# quadcopter.net
KiCad netlist of a schematic drawn in EAGLE
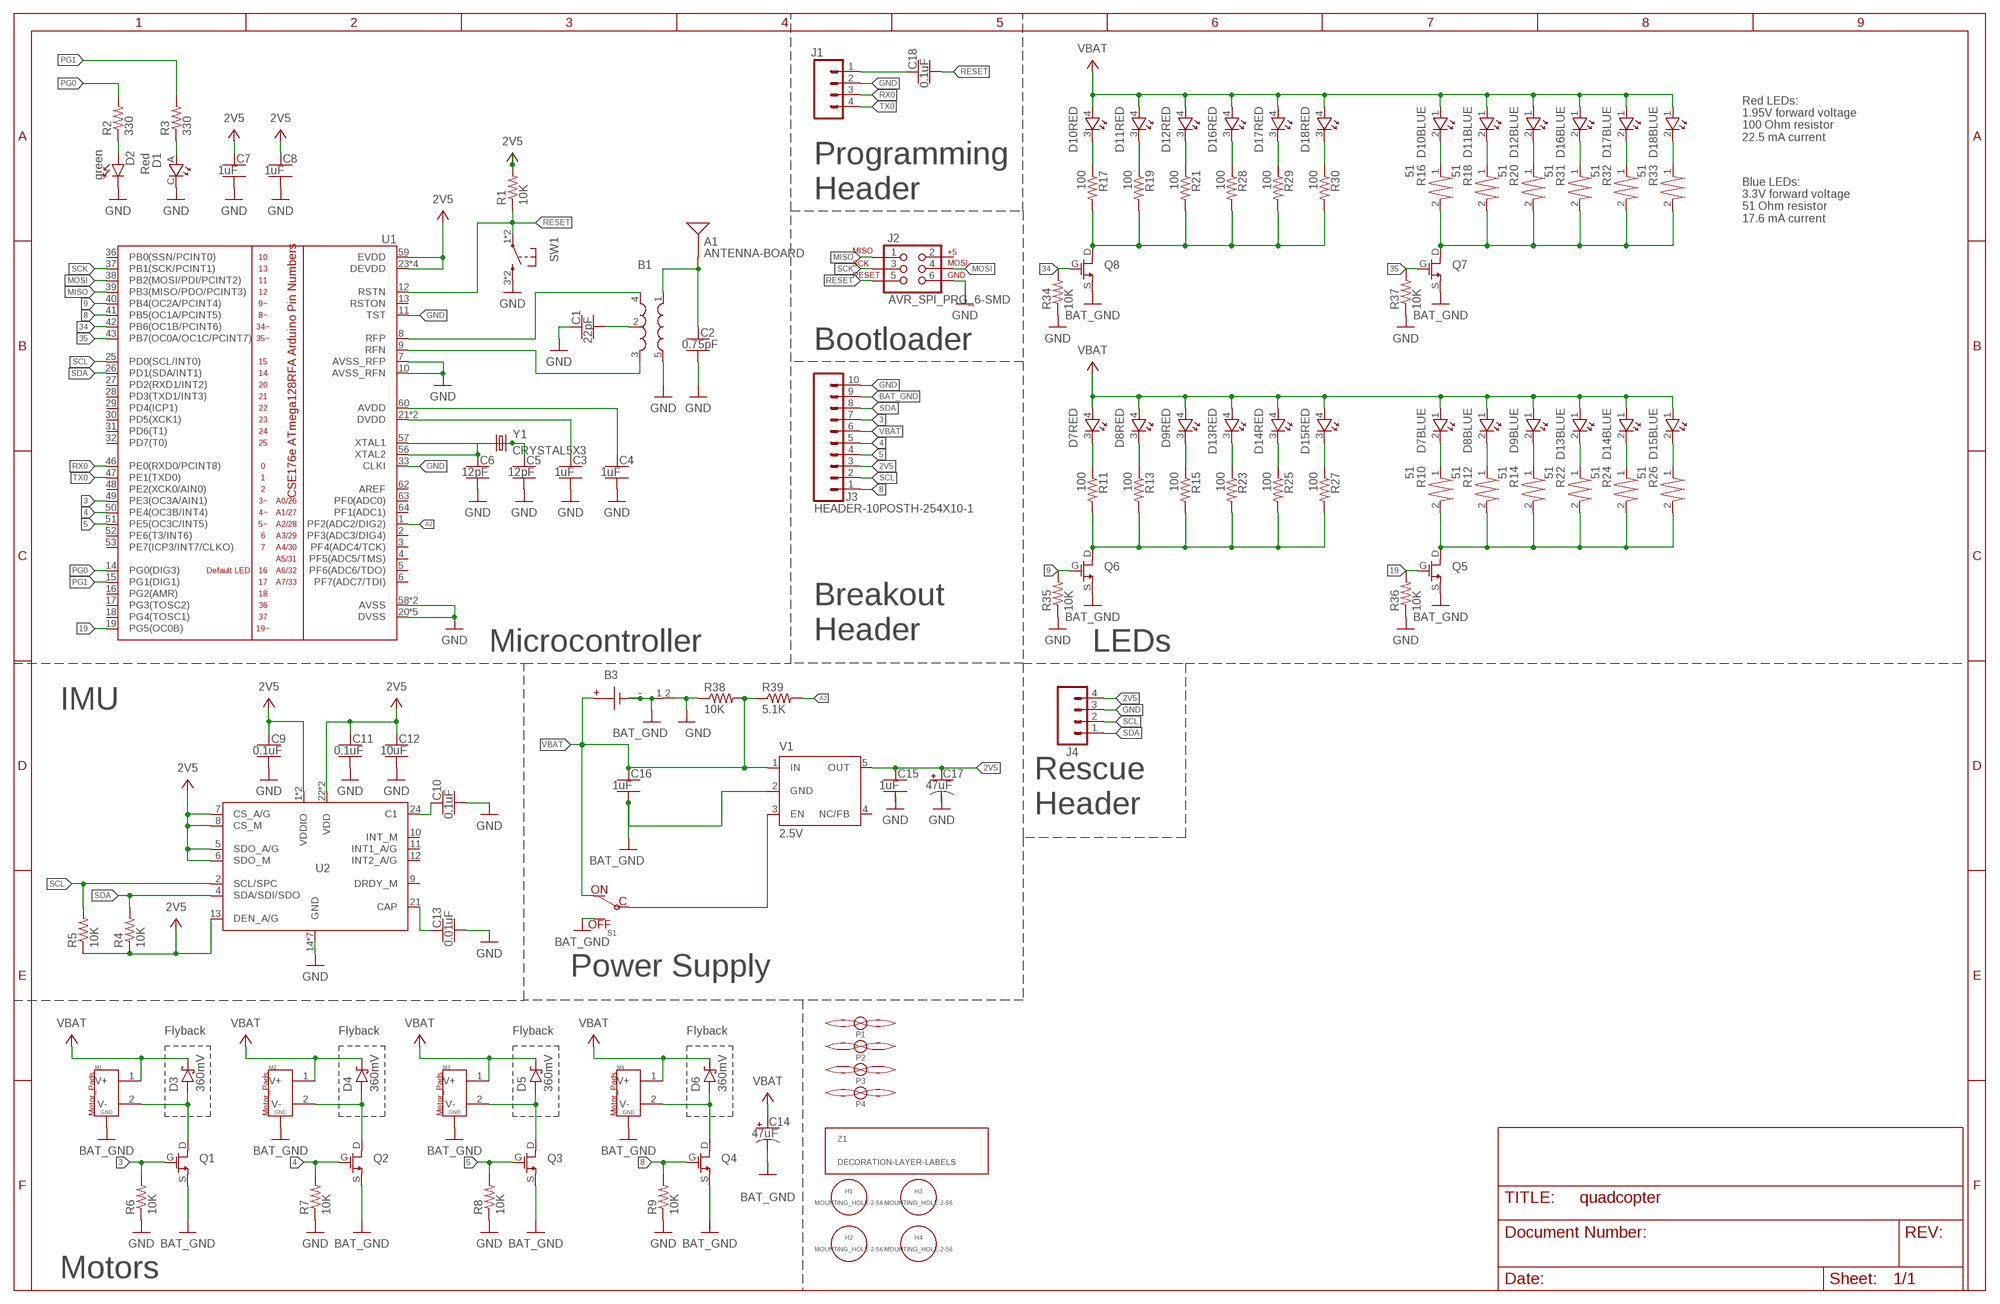
[diagram p0: schematic, sheet 1]

(export (version "E")
  (design (tool "Eeschema 10.0.6"))
  (components
    (comp (ref "A1")
      (value "ANTENNA-BOARD")
      (footprint "eagle-import:ANT_PCB_2.4GHZ_NRF8001_1.6MM_1OZ")
      (fields (field (name "MFR") "NA") (field (name "CREATOR") "Swanson"))
      (libsource (lib "eagle-import") (part "ANTENNA-BOARD"))
    )
    (comp (ref "B1")
      (value "BALUN0805")
      (footprint "eagle-import:BALUN")
      (fields
        (field (name "MFR") "Wurth Electronics Inc.")
        (field (name "MPN") "748421245")
        (field (name "CREATOR") "Swanson")
        (field (name "REVIEWER") "Swanson")
      )
      (libsource (lib "eagle-import") (part "BALUN0805"))
    )
    (comp (ref "B3")
      (value "BATTERY-SMD-TH")
      (footprint "eagle-import:BATTERY-COMBO")
      (libsource (lib "eagle-import") (part "BATTERY-SMD-TH"))
    )
    (comp (ref "C1")
      (value "22pF")
      (footprint "eagle-import:CAPC2012X140_HS")
      (fields
        (field (name "MFR") "Murata Electronics")
        (field (name "MPN") "GRM21A5C2E220JW01D")
        (field (name "CREATOR") "Swanson")
        (field (name "REVIEWER") "Swanson")
      )
      (libsource (lib "eagle-import") (part "CAPACITOR-NP_SMD-2012-0805_CERAMIC-22PF"))
    )
    (comp (ref "C2")
      (value "0.75pF")
      (footprint "eagle-import:CAPC2012X140_HS")
      (fields
        (field (name "MFR") "Murata Electronics")
        (field (name "MPN") "GQM2195C2AR75CB01D")
        (field (name "CREATOR") "Swanson")
        (field (name "REVIEWER") "Swanson")
      )
      (libsource (lib "eagle-import") (part "CAPACITOR-NP_SMD-2012-0805_CERAMIC-0.75PF"))
    )
    (comp (ref "C3")
      (value "1uF")
      (footprint "eagle-import:CAPC2012X140_HS")
      (fields
        (field (name "MFR") "Taiyo Yuden")
        (field (name "MPN") "TMK212B7105KG-T")
        (field (name "CREATOR") "Swanson")
        (field (name "REVIEWER") "Swanson")
      )
      (libsource (lib "eagle-import") (part "CAPACITOR-NP_SMD-2012-0805_CERAMIC-1UF"))
    )
    (comp (ref "C4")
      (value "1uF")
      (footprint "eagle-import:CAPC2012X140_HS")
      (fields
        (field (name "MFR") "Taiyo Yuden")
        (field (name "MPN") "TMK212B7105KG-T")
        (field (name "CREATOR") "Swanson")
        (field (name "REVIEWER") "Swanson")
      )
      (libsource (lib "eagle-import") (part "CAPACITOR-NP_SMD-2012-0805_CERAMIC-1UF"))
    )
    (comp (ref "C5")
      (value "12pF")
      (footprint "eagle-import:CAPC2012X140_HS")
      (fields
        (field (name "MFR") "Murata Electronics")
        (field (name "MPN") "GRM21A5C2E120JW01D")
        (field (name "CREATOR") "Swanson")
        (field (name "REVIEWER") "Swanson")
      )
      (libsource (lib "eagle-import") (part "CAPACITOR-NP_SMD-2012-0805_CERAMIC-12PF"))
    )
    (comp (ref "C6")
      (value "12pF")
      (footprint "eagle-import:CAPC2012X140_HS")
      (fields
        (field (name "MFR") "Murata Electronics")
        (field (name "MPN") "GRM21A5C2E120JW01D")
        (field (name "CREATOR") "Swanson")
        (field (name "REVIEWER") "Swanson")
      )
      (libsource (lib "eagle-import") (part "CAPACITOR-NP_SMD-2012-0805_CERAMIC-12PF"))
    )
    (comp (ref "C7")
      (value "1uF")
      (footprint "eagle-import:CAPC2012X140_HS")
      (fields
        (field (name "MFR") "Taiyo Yuden")
        (field (name "MPN") "TMK212B7105KG-T")
        (field (name "CREATOR") "Swanson")
        (field (name "REVIEWER") "Swanson")
      )
      (libsource (lib "eagle-import") (part "CAPACITOR-NP_SMD-2012-0805_CERAMIC-1UF"))
    )
    (comp (ref "C8")
      (value "1uF")
      (footprint "eagle-import:CAPC2012X140_HS")
      (fields
        (field (name "MFR") "Taiyo Yuden")
        (field (name "MPN") "TMK212B7105KG-T")
        (field (name "CREATOR") "Swanson")
        (field (name "REVIEWER") "Swanson")
      )
      (libsource (lib "eagle-import") (part "CAPACITOR-NP_SMD-2012-0805_CERAMIC-1UF"))
    )
    (comp (ref "C9")
      (value "0.1uF")
      (footprint "eagle-import:CAPC2012X140_HS")
      (fields
        (field (name "MFR") "TDK Corporation")
        (field (name "MPN") "C2012X7R2A104K125AA")
        (field (name "CREATOR") "Swanson")
        (field (name "REVIEWER") "Swanson")
      )
      (libsource (lib "eagle-import") (part "CAPACITOR-NP_SMD-2012-0805_CERAMIC-0.1UF"))
    )
    (comp (ref "C10")
      (value "0.1uF")
      (footprint "eagle-import:CAPC2012X140_HS")
      (fields
        (field (name "MFR") "TDK Corporation")
        (field (name "MPN") "C2012X7R2A104K125AA")
        (field (name "CREATOR") "Swanson")
        (field (name "REVIEWER") "Swanson")
      )
      (libsource (lib "eagle-import") (part "CAPACITOR-NP_SMD-2012-0805_CERAMIC-0.1UF"))
    )
    (comp (ref "C11")
      (value "0.1uF")
      (footprint "eagle-import:CAPC2012X140_HS")
      (fields
        (field (name "MFR") "TDK Corporation")
        (field (name "MPN") "C2012X7R2A104K125AA")
        (field (name "CREATOR") "Swanson")
        (field (name "REVIEWER") "Swanson")
      )
      (libsource (lib "eagle-import") (part "CAPACITOR-NP_SMD-2012-0805_CERAMIC-0.1UF"))
    )
    (comp (ref "C12")
      (value "10uF")
      (footprint "eagle-import:CAPC2012X140_HS")
      (fields
        (field (name "MFR") "TDK")
        (field (name "MPN") "C2012X5R1E106K125AB")
        (field (name "CREATOR") "Swanson")
        (field (name "REVIEWER") "Swanson")
      )
      (libsource (lib "eagle-import") (part "CAPACITOR-NP_SMD-2012-0805_CERAMIC-10UF"))
    )
    (comp (ref "C13")
      (value "0.01uF")
      (footprint "eagle-import:CAPC2012X140_HS")
      (fields
        (field (name "MFR") "Knowles Syfer")
        (field (name "MPN") "0805J0500104KJT")
        (field (name "CREATOR") "Swanson")
        (field (name "REVIEWER") "Swanson")
      )
      (libsource (lib "eagle-import") (part "CAPACITOR-NP_SMD-2012-0805_CERAMIC-0.01UF"))
    )
    (comp (ref "C14")
      (value "47uF")
      (footprint "eagle-import:CAPMP3216X180")
      (fields
        (field (name "MFR") "AVX Corporation")
        (field (name "MPN") "TAJA476K006SNJV")
        (field (name "CREATOR") "Swanson")
      )
      (libsource (lib "eagle-import") (part "CAPACITOR-POL_47UF-SMD-1206-TAJA"))
    )
    (comp (ref "C15")
      (value "1uF")
      (footprint "eagle-import:CAPC2012X140_HS")
      (fields
        (field (name "MFR") "Taiyo Yuden")
        (field (name "MPN") "TMK212B7105KG-T")
        (field (name "CREATOR") "Swanson")
        (field (name "REVIEWER") "Swanson")
      )
      (libsource (lib "eagle-import") (part "CAPACITOR-NP_SMD-2012-0805_CERAMIC-1UF"))
    )
    (comp (ref "C16")
      (value "1uF")
      (footprint "eagle-import:CAPC2012X140_HS")
      (fields
        (field (name "MFR") "Taiyo Yuden")
        (field (name "MPN") "TMK212B7105KG-T")
        (field (name "CREATOR") "Swanson")
        (field (name "REVIEWER") "Swanson")
      )
      (libsource (lib "eagle-import") (part "CAPACITOR-NP_SMD-2012-0805_CERAMIC-1UF"))
    )
    (comp (ref "C17")
      (value "47uF")
      (footprint "eagle-import:CAPMP3216X180")
      (fields
        (field (name "MFR") "AVX Corporation")
        (field (name "MPN") "TAJA476K006SNJV")
        (field (name "CREATOR") "Swanson")
      )
      (libsource (lib "eagle-import") (part "CAPACITOR-POL_47UF-SMD-1206-TAJA"))
    )
    (comp (ref "C18")
      (value "0.1uF")
      (footprint "eagle-import:CAPC2012X140_HS")
      (fields
        (field (name "MFR") "TDK Corporation")
        (field (name "MPN") "C2012X7R2A104K125AA")
        (field (name "CREATOR") "Swanson")
        (field (name "REVIEWER") "Swanson")
      )
      (libsource (lib "eagle-import") (part "CAPACITOR-NP_SMD-2012-0805_CERAMIC-0.1UF"))
    )
    (comp (ref "D1")
      (value "Red")
      (footprint "eagle-import:0805_LED")
      (fields (field (name "CREATOR") "Rye Gleason"))
      (libsource (lib "eagle-import") (part "LED-RED-0805"))
    )
    (comp (ref "D2")
      (value "green")
      (footprint "eagle-import:LEDSC125X200X120-2_HS")
      (fields
        (field (name "MFR") "Lite-On Inc")
        (field (name "MPN") "LTST-C170GKT")
        (field (name "CREATOR") "Swanson")
        (field (name "REVIEWER") "Swanson")
      )
      (libsource (lib "eagle-import") (part "DIODE-LED_SMD-2012-0805-GREEN"))
    )
    (comp (ref "D3")
      (value "360mV")
      (footprint "eagle-import:SODFL3516X96")
      (fields
        (field (name "MFR") "Toshiba Semiconductor and Storage")
        (field (name "MPN") "CRS08(TE85L,Q,M)")
        (field (name "CREATOR") "Swanson")
        (field (name "REVIEWER") "Swanson")
      )
      (libsource (lib "eagle-import") (part "DIODE-SCHOTTKY_-SMD-SOD123"))
    )
    (comp (ref "D4")
      (value "360mV")
      (footprint "eagle-import:SODFL3516X96")
      (fields
        (field (name "MFR") "Toshiba Semiconductor and Storage")
        (field (name "MPN") "CRS08(TE85L,Q,M)")
        (field (name "CREATOR") "Swanson")
        (field (name "REVIEWER") "Swanson")
      )
      (libsource (lib "eagle-import") (part "DIODE-SCHOTTKY_-SMD-SOD123"))
    )
    (comp (ref "D5")
      (value "360mV")
      (footprint "eagle-import:SODFL3516X96")
      (fields
        (field (name "MFR") "Toshiba Semiconductor and Storage")
        (field (name "MPN") "CRS08(TE85L,Q,M)")
        (field (name "CREATOR") "Swanson")
        (field (name "REVIEWER") "Swanson")
      )
      (libsource (lib "eagle-import") (part "DIODE-SCHOTTKY_-SMD-SOD123"))
    )
    (comp (ref "D6")
      (value "360mV")
      (footprint "eagle-import:SODFL3516X96")
      (fields
        (field (name "MFR") "Toshiba Semiconductor and Storage")
        (field (name "MPN") "CRS08(TE85L,Q,M)")
        (field (name "CREATOR") "Swanson")
        (field (name "REVIEWER") "Swanson")
      )
      (libsource (lib "eagle-import") (part "DIODE-SCHOTTKY_-SMD-SOD123"))
    )
    (comp (ref "D7")
      (value "DUAL_LED0805_RB_LED")
      (footprint "eagle-import:0805_RB_LED")
      (fields (field (name "CREATOR") "Rye Gleason"))
      (libsource (lib "eagle-import") (part "DUAL_LED0805_RB_LED"))
    )
    (comp (ref "D8")
      (value "DUAL_LED0805_RB_LED")
      (footprint "eagle-import:0805_RB_LED")
      (fields (field (name "CREATOR") "Rye Gleason"))
      (libsource (lib "eagle-import") (part "DUAL_LED0805_RB_LED"))
    )
    (comp (ref "D9")
      (value "DUAL_LED0805_RB_LED")
      (footprint "eagle-import:0805_RB_LED")
      (fields (field (name "CREATOR") "Rye Gleason"))
      (libsource (lib "eagle-import") (part "DUAL_LED0805_RB_LED"))
    )
    (comp (ref "D10")
      (value "DUAL_LED0805_RB_LED")
      (footprint "eagle-import:0805_RB_LED")
      (fields (field (name "CREATOR") "Rye Gleason"))
      (libsource (lib "eagle-import") (part "DUAL_LED0805_RB_LED"))
    )
    (comp (ref "D11")
      (value "DUAL_LED0805_RB_LED")
      (footprint "eagle-import:0805_RB_LED")
      (fields (field (name "CREATOR") "Rye Gleason"))
      (libsource (lib "eagle-import") (part "DUAL_LED0805_RB_LED"))
    )
    (comp (ref "D12")
      (value "DUAL_LED0805_RB_LED")
      (footprint "eagle-import:0805_RB_LED")
      (fields (field (name "CREATOR") "Rye Gleason"))
      (libsource (lib "eagle-import") (part "DUAL_LED0805_RB_LED"))
    )
    (comp (ref "D13")
      (value "DUAL_LED0805_RB_LED")
      (footprint "eagle-import:0805_RB_LED")
      (fields (field (name "CREATOR") "Rye Gleason"))
      (libsource (lib "eagle-import") (part "DUAL_LED0805_RB_LED"))
    )
    (comp (ref "D14")
      (value "DUAL_LED0805_RB_LED")
      (footprint "eagle-import:0805_RB_LED")
      (fields (field (name "CREATOR") "Rye Gleason"))
      (libsource (lib "eagle-import") (part "DUAL_LED0805_RB_LED"))
    )
    (comp (ref "D15")
      (value "DUAL_LED0805_RB_LED")
      (footprint "eagle-import:0805_RB_LED")
      (fields (field (name "CREATOR") "Rye Gleason"))
      (libsource (lib "eagle-import") (part "DUAL_LED0805_RB_LED"))
    )
    (comp (ref "D16")
      (value "DUAL_LED0805_RB_LED")
      (footprint "eagle-import:0805_RB_LED")
      (fields (field (name "CREATOR") "Rye Gleason"))
      (libsource (lib "eagle-import") (part "DUAL_LED0805_RB_LED"))
    )
    (comp (ref "D17")
      (value "DUAL_LED0805_RB_LED")
      (footprint "eagle-import:0805_RB_LED")
      (fields (field (name "CREATOR") "Rye Gleason"))
      (libsource (lib "eagle-import") (part "DUAL_LED0805_RB_LED"))
    )
    (comp (ref "D18")
      (value "DUAL_LED0805_RB_LED")
      (footprint "eagle-import:0805_RB_LED")
      (fields (field (name "CREATOR") "Rye Gleason"))
      (libsource (lib "eagle-import") (part "DUAL_LED0805_RB_LED"))
    )
    (comp (ref "H1")
      (value "MOUNTING_HOLE-2-56")
      (footprint "eagle-import:2-56-MOUNTING-HOLE-NO-METAL")
      (libsource (lib "eagle-import") (part "MOUNTING_HOLE-2-56"))
    )
    (comp (ref "H2")
      (value "MOUNTING_HOLE-2-56")
      (footprint "eagle-import:2-56-MOUNTING-HOLE-NO-METAL")
      (libsource (lib "eagle-import") (part "MOUNTING_HOLE-2-56"))
    )
    (comp (ref "H3")
      (value "MOUNTING_HOLE-2-56")
      (footprint "eagle-import:2-56-MOUNTING-HOLE-NO-METAL")
      (libsource (lib "eagle-import") (part "MOUNTING_HOLE-2-56"))
    )
    (comp (ref "H4")
      (value "MOUNTING_HOLE-2-56")
      (footprint "eagle-import:2-56-MOUNTING-HOLE-NO-METAL")
      (libsource (lib "eagle-import") (part "MOUNTING_HOLE-2-56"))
    )
    (comp (ref "J1")
      (value "HEADER-4POS-0.1IN-FEMALE-SMD-BOTTOM-ENTRY")
      (footprint "eagle-import:HEADER-1X4-BOTTOM-ENTRY")
      (fields
        (field (name "MFR") "TE Connectivity AMP Connectors")
        (field (name "MPN") "1241152-4")
        (field (name "CREATOR") "Swanson")
      )
      (libsource (lib "eagle-import") (part "HEADER-4POS-0.1IN-FEMALE-SMD-BOTTOM-ENTRY"))
    )
    (comp (ref "J2")
      (value "AVR_SPI_PRG_6-SMD")
      (footprint "eagle-import:2X3-SMD")
      (fields
        (field (name "MFR") "Amphenol ICC (FCI)")
        (field (name "MPN") "95278-101A06LF")
        (field (name "CREATOR") "Swanson")
      )
      (libsource (lib "eagle-import") (part "AVR_SPI_PRG_6-SMD"))
    )
    (comp (ref "J3")
      (value "HEADER-10POSTH-254X10-1")
      (footprint "eagle-import:HDRV10W63P254_10X1_2540X254H838_HS")
      (fields
        (field (name "MFR") "Amphenol FCI")
        (field (name "MPN") "68000-110HLF")
        (field (name "CREATOR") "Swanson")
        (field (name "REVIEWER") "Swanson")
      )
      (libsource (lib "eagle-import") (part "HEADER-10POSTH-254X10-1"))
    )
    (comp (ref "J4")
      (value "HEADER-4POS-0.1IN-FEMALE")
      (footprint "eagle-import:HDRVR4W80P254_1X4_1066X254X850B")
      (fields (field (name "CREATOR") "Swanson"))
      (libsource (lib "eagle-import") (part "HEADER-4POS-0.1IN-FEMALE"))
    )
    (comp (ref "M1")
      (value "MOTOR_PADS_GND-MOLEX-SMD")
      (footprint "eagle-import:MOLEX-0532610271")
      (fields
        (field (name "MFR") "Molex")
        (field (name "MPN") "532610271")
        (field (name "CREATOR") "Swanson")
      )
      (libsource (lib "eagle-import") (part "MOTOR_PADS_GND-MOLEX-SMD"))
    )
    (comp (ref "M2")
      (value "MOTOR_PADS_GND-MOLEX-SMD")
      (footprint "eagle-import:MOLEX-0532610271")
      (fields
        (field (name "MFR") "Molex")
        (field (name "MPN") "532610271")
        (field (name "CREATOR") "Swanson")
      )
      (libsource (lib "eagle-import") (part "MOTOR_PADS_GND-MOLEX-SMD"))
    )
    (comp (ref "M3")
      (value "MOTOR_PADS_GND-MOLEX-SMD")
      (footprint "eagle-import:MOLEX-0532610271")
      (fields
        (field (name "MFR") "Molex")
        (field (name "MPN") "532610271")
        (field (name "CREATOR") "Swanson")
      )
      (libsource (lib "eagle-import") (part "MOTOR_PADS_GND-MOLEX-SMD"))
    )
    (comp (ref "M4")
      (value "MOTOR_PADS_GND-MOLEX-SMD")
      (footprint "eagle-import:MOLEX-0532610271")
      (fields
        (field (name "MFR") "Molex")
        (field (name "MPN") "532610271")
        (field (name "CREATOR") "Swanson")
      )
      (libsource (lib "eagle-import") (part "MOTOR_PADS_GND-MOLEX-SMD"))
    )
    (comp (ref "P1")
      (value "PROPELLOR-45MM")
      (footprint "eagle-import:MOTOR_AND_PROP")
      (libsource (lib "eagle-import") (part "PROPELLOR-45MM"))
    )
    (comp (ref "P2")
      (value "PROPELLOR-45MM")
      (footprint "eagle-import:MOTOR_AND_PROP")
      (libsource (lib "eagle-import") (part "PROPELLOR-45MM"))
    )
    (comp (ref "P3")
      (value "PROPELLOR-45MM")
      (footprint "eagle-import:MOTOR_AND_PROP")
      (libsource (lib "eagle-import") (part "PROPELLOR-45MM"))
    )
    (comp (ref "P4")
      (value "PROPELLOR-45MM")
      (footprint "eagle-import:MOTOR_AND_PROP")
      (libsource (lib "eagle-import") (part "PROPELLOR-45MM"))
    )
    (comp (ref "Q1")
      (value "NMOSFETSI2302CDS-T1-E3CT-ND")
      (footprint "eagle-import:SOT23_MOSFET")
      (fields (field (name "CREATOR") "Rye Gleason"))
      (libsource (lib "eagle-import") (part "NMOSFETSI2302CDS-T1-E3CT-ND"))
    )
    (comp (ref "Q2")
      (value "NMOSFETSI2302CDS-T1-E3CT-ND")
      (footprint "eagle-import:SOT23_MOSFET")
      (fields (field (name "CREATOR") "Rye Gleason"))
      (libsource (lib "eagle-import") (part "NMOSFETSI2302CDS-T1-E3CT-ND"))
    )
    (comp (ref "Q3")
      (value "NMOSFETSI2302CDS-T1-E3CT-ND")
      (footprint "eagle-import:SOT23_MOSFET")
      (fields (field (name "CREATOR") "Rye Gleason"))
      (libsource (lib "eagle-import") (part "NMOSFETSI2302CDS-T1-E3CT-ND"))
    )
    (comp (ref "Q4")
      (value "NMOSFETSI2302CDS-T1-E3CT-ND")
      (footprint "eagle-import:SOT23_MOSFET")
      (fields (field (name "CREATOR") "Rye Gleason"))
      (libsource (lib "eagle-import") (part "NMOSFETSI2302CDS-T1-E3CT-ND"))
    )
    (comp (ref "Q5")
      (value "NMOSFETSI2302CDS-T1-E3CT-ND")
      (footprint "eagle-import:SOT23_MOSFET")
      (fields (field (name "CREATOR") "Rye Gleason"))
      (libsource (lib "eagle-import") (part "NMOSFETSI2302CDS-T1-E3CT-ND"))
    )
    (comp (ref "Q6")
      (value "NMOSFETSI2302CDS-T1-E3CT-ND")
      (footprint "eagle-import:SOT23_MOSFET")
      (fields (field (name "CREATOR") "Rye Gleason"))
      (libsource (lib "eagle-import") (part "NMOSFETSI2302CDS-T1-E3CT-ND"))
    )
    (comp (ref "Q7")
      (value "NMOSFETSI2302CDS-T1-E3CT-ND")
      (footprint "eagle-import:SOT23_MOSFET")
      (fields (field (name "CREATOR") "Rye Gleason"))
      (libsource (lib "eagle-import") (part "NMOSFETSI2302CDS-T1-E3CT-ND"))
    )
    (comp (ref "Q8")
      (value "NMOSFETSI2302CDS-T1-E3CT-ND")
      (footprint "eagle-import:SOT23_MOSFET")
      (fields (field (name "CREATOR") "Rye Gleason"))
      (libsource (lib "eagle-import") (part "NMOSFETSI2302CDS-T1-E3CT-ND"))
    )
    (comp (ref "R1")
      (value "10K")
      (footprint "eagle-import:RESC2012X60_HS")
      (fields
        (field (name "MFR") "Yageo")
        (field (name "MPN") "RC0805JR-0710KL")
        (field (name "CREATOR") "Swanson")
        (field (name "REVIEWER") "Swanson")
      )
      (libsource (lib "eagle-import") (part "RESISTOR_SMD-2012-0805-10K"))
    )
    (comp (ref "R2")
      (value "330")
      (footprint "eagle-import:RESC2012X60_HS")
      (fields
        (field (name "MFR") "Yageo")
        (field (name "MPN") "RC0805JR-07330RL")
        (field (name "CREATOR") "Swanson")
        (field (name "REVIEWER") "Swanson")
      )
      (libsource (lib "eagle-import") (part "RESISTOR_SMD-2012-0805-330"))
    )
    (comp (ref "R3")
      (value "330")
      (footprint "eagle-import:RESC2012X60_HS")
      (fields
        (field (name "MFR") "Yageo")
        (field (name "MPN") "RC0805JR-07330RL")
        (field (name "CREATOR") "Swanson")
        (field (name "REVIEWER") "Swanson")
      )
      (libsource (lib "eagle-import") (part "RESISTOR_SMD-2012-0805-330"))
    )
    (comp (ref "R4")
      (value "10K")
      (footprint "eagle-import:RESC2012X60_HS")
      (fields
        (field (name "MFR") "Yageo")
        (field (name "MPN") "RC0805JR-0710KL")
        (field (name "CREATOR") "Swanson")
        (field (name "REVIEWER") "Swanson")
      )
      (libsource (lib "eagle-import") (part "RESISTOR_SMD-2012-0805-10K"))
    )
    (comp (ref "R5")
      (value "10K")
      (footprint "eagle-import:RESC2012X60_HS")
      (fields
        (field (name "MFR") "Yageo")
        (field (name "MPN") "RC0805JR-0710KL")
        (field (name "CREATOR") "Swanson")
        (field (name "REVIEWER") "Swanson")
      )
      (libsource (lib "eagle-import") (part "RESISTOR_SMD-2012-0805-10K"))
    )
    (comp (ref "R6")
      (value "10K")
      (footprint "eagle-import:RESC2012X60_HS")
      (fields
        (field (name "MFR") "Yageo")
        (field (name "MPN") "RC0805JR-0710KL")
        (field (name "CREATOR") "Swanson")
        (field (name "REVIEWER") "Swanson")
      )
      (libsource (lib "eagle-import") (part "RESISTOR_SMD-2012-0805-10K"))
    )
    (comp (ref "R7")
      (value "10K")
      (footprint "eagle-import:RESC2012X60_HS")
      (fields
        (field (name "MFR") "Yageo")
        (field (name "MPN") "RC0805JR-0710KL")
        (field (name "CREATOR") "Swanson")
        (field (name "REVIEWER") "Swanson")
      )
      (libsource (lib "eagle-import") (part "RESISTOR_SMD-2012-0805-10K"))
    )
    (comp (ref "R8")
      (value "10K")
      (footprint "eagle-import:RESC2012X60_HS")
      (fields
        (field (name "MFR") "Yageo")
        (field (name "MPN") "RC0805JR-0710KL")
        (field (name "CREATOR") "Swanson")
        (field (name "REVIEWER") "Swanson")
      )
      (libsource (lib "eagle-import") (part "RESISTOR_SMD-2012-0805-10K"))
    )
    (comp (ref "R9")
      (value "10K")
      (footprint "eagle-import:RESC2012X60_HS")
      (fields
        (field (name "MFR") "Yageo")
        (field (name "MPN") "RC0805JR-0710KL")
        (field (name "CREATOR") "Swanson")
        (field (name "REVIEWER") "Swanson")
      )
      (libsource (lib "eagle-import") (part "RESISTOR_SMD-2012-0805-10K"))
    )
    (comp (ref "R10")
      (value "51")
      (footprint "eagle-import:0805_RESISTOR")
      (fields (field (name "CREATOR") "Rye Gleason"))
      (libsource (lib "eagle-import") (part "RESISTOR-0805-51OHM"))
    )
    (comp (ref "R11")
      (value "100")
      (footprint "eagle-import:RESC2012X60_HS")
      (fields
        (field (name "MFR") "Yageo")
        (field (name "MPN") "RC0805JR-07100RL")
        (field (name "CREATOR") "Swanson")
        (field (name "REVIEWER") "Swanson")
      )
      (libsource (lib "eagle-import") (part "RESISTOR_SMD-2012-0805-100"))
    )
    (comp (ref "R12")
      (value "51")
      (footprint "eagle-import:0805_RESISTOR")
      (fields (field (name "CREATOR") "Rye Gleason"))
      (libsource (lib "eagle-import") (part "RESISTOR-0805-51OHM"))
    )
    (comp (ref "R13")
      (value "100")
      (footprint "eagle-import:RESC2012X60_HS")
      (fields
        (field (name "MFR") "Yageo")
        (field (name "MPN") "RC0805JR-07100RL")
        (field (name "CREATOR") "Swanson")
        (field (name "REVIEWER") "Swanson")
      )
      (libsource (lib "eagle-import") (part "RESISTOR_SMD-2012-0805-100"))
    )
    (comp (ref "R14")
      (value "51")
      (footprint "eagle-import:0805_RESISTOR")
      (fields (field (name "CREATOR") "Rye Gleason"))
      (libsource (lib "eagle-import") (part "RESISTOR-0805-51OHM"))
    )
    (comp (ref "R15")
      (value "100")
      (footprint "eagle-import:RESC2012X60_HS")
      (fields
        (field (name "MFR") "Yageo")
        (field (name "MPN") "RC0805JR-07100RL")
        (field (name "CREATOR") "Swanson")
        (field (name "REVIEWER") "Swanson")
      )
      (libsource (lib "eagle-import") (part "RESISTOR_SMD-2012-0805-100"))
    )
    (comp (ref "R16")
      (value "51")
      (footprint "eagle-import:0805_RESISTOR")
      (fields (field (name "CREATOR") "Rye Gleason"))
      (libsource (lib "eagle-import") (part "RESISTOR-0805-51OHM"))
    )
    (comp (ref "R17")
      (value "100")
      (footprint "eagle-import:RESC2012X60_HS")
      (fields
        (field (name "MFR") "Yageo")
        (field (name "MPN") "RC0805JR-07100RL")
        (field (name "CREATOR") "Swanson")
        (field (name "REVIEWER") "Swanson")
      )
      (libsource (lib "eagle-import") (part "RESISTOR_SMD-2012-0805-100"))
    )
    (comp (ref "R18")
      (value "51")
      (footprint "eagle-import:0805_RESISTOR")
      (fields (field (name "CREATOR") "Rye Gleason"))
      (libsource (lib "eagle-import") (part "RESISTOR-0805-51OHM"))
    )
    (comp (ref "R19")
      (value "100")
      (footprint "eagle-import:RESC2012X60_HS")
      (fields
        (field (name "MFR") "Yageo")
        (field (name "MPN") "RC0805JR-07100RL")
        (field (name "CREATOR") "Swanson")
        (field (name "REVIEWER") "Swanson")
      )
      (libsource (lib "eagle-import") (part "RESISTOR_SMD-2012-0805-100"))
    )
    (comp (ref "R20")
      (value "51")
      (footprint "eagle-import:0805_RESISTOR")
      (fields (field (name "CREATOR") "Rye Gleason"))
      (libsource (lib "eagle-import") (part "RESISTOR-0805-51OHM"))
    )
    (comp (ref "R21")
      (value "100")
      (footprint "eagle-import:RESC2012X60_HS")
      (fields
        (field (name "MFR") "Yageo")
        (field (name "MPN") "RC0805JR-07100RL")
        (field (name "CREATOR") "Swanson")
        (field (name "REVIEWER") "Swanson")
      )
      (libsource (lib "eagle-import") (part "RESISTOR_SMD-2012-0805-100"))
    )
    (comp (ref "R22")
      (value "51")
      (footprint "eagle-import:0805_RESISTOR")
      (fields (field (name "CREATOR") "Rye Gleason"))
      (libsource (lib "eagle-import") (part "RESISTOR-0805-51OHM"))
    )
    (comp (ref "R23")
      (value "100")
      (footprint "eagle-import:RESC2012X60_HS")
      (fields
        (field (name "MFR") "Yageo")
        (field (name "MPN") "RC0805JR-07100RL")
        (field (name "CREATOR") "Swanson")
        (field (name "REVIEWER") "Swanson")
      )
      (libsource (lib "eagle-import") (part "RESISTOR_SMD-2012-0805-100"))
    )
    (comp (ref "R24")
      (value "51")
      (footprint "eagle-import:0805_RESISTOR")
      (fields (field (name "CREATOR") "Rye Gleason"))
      (libsource (lib "eagle-import") (part "RESISTOR-0805-51OHM"))
    )
    (comp (ref "R25")
      (value "100")
      (footprint "eagle-import:RESC2012X60_HS")
      (fields
        (field (name "MFR") "Yageo")
        (field (name "MPN") "RC0805JR-07100RL")
        (field (name "CREATOR") "Swanson")
        (field (name "REVIEWER") "Swanson")
      )
      (libsource (lib "eagle-import") (part "RESISTOR_SMD-2012-0805-100"))
    )
    (comp (ref "R26")
      (value "51")
      (footprint "eagle-import:0805_RESISTOR")
      (fields (field (name "CREATOR") "Rye Gleason"))
      (libsource (lib "eagle-import") (part "RESISTOR-0805-51OHM"))
    )
    (comp (ref "R27")
      (value "100")
      (footprint "eagle-import:RESC2012X60_HS")
      (fields
        (field (name "MFR") "Yageo")
        (field (name "MPN") "RC0805JR-07100RL")
        (field (name "CREATOR") "Swanson")
        (field (name "REVIEWER") "Swanson")
      )
      (libsource (lib "eagle-import") (part "RESISTOR_SMD-2012-0805-100"))
    )
    (comp (ref "R28")
      (value "100")
      (footprint "eagle-import:RESC2012X60_HS")
      (fields
        (field (name "MFR") "Yageo")
        (field (name "MPN") "RC0805JR-07100RL")
        (field (name "CREATOR") "Swanson")
        (field (name "REVIEWER") "Swanson")
      )
      (libsource (lib "eagle-import") (part "RESISTOR_SMD-2012-0805-100"))
    )
    (comp (ref "R29")
      (value "100")
      (footprint "eagle-import:RESC2012X60_HS")
      (fields
        (field (name "MFR") "Yageo")
        (field (name "MPN") "RC0805JR-07100RL")
        (field (name "CREATOR") "Swanson")
        (field (name "REVIEWER") "Swanson")
      )
      (libsource (lib "eagle-import") (part "RESISTOR_SMD-2012-0805-100"))
    )
    (comp (ref "R30")
      (value "100")
      (footprint "eagle-import:RESC2012X60_HS")
      (fields
        (field (name "MFR") "Yageo")
        (field (name "MPN") "RC0805JR-07100RL")
        (field (name "CREATOR") "Swanson")
        (field (name "REVIEWER") "Swanson")
      )
      (libsource (lib "eagle-import") (part "RESISTOR_SMD-2012-0805-100"))
    )
    (comp (ref "R31")
      (value "51")
      (footprint "eagle-import:0805_RESISTOR")
      (fields (field (name "CREATOR") "Rye Gleason"))
      (libsource (lib "eagle-import") (part "RESISTOR-0805-51OHM"))
    )
    (comp (ref "R32")
      (value "51")
      (footprint "eagle-import:0805_RESISTOR")
      (fields (field (name "CREATOR") "Rye Gleason"))
      (libsource (lib "eagle-import") (part "RESISTOR-0805-51OHM"))
    )
    (comp (ref "R33")
      (value "51")
      (footprint "eagle-import:0805_RESISTOR")
      (fields (field (name "CREATOR") "Rye Gleason"))
      (libsource (lib "eagle-import") (part "RESISTOR-0805-51OHM"))
    )
    (comp (ref "R34")
      (value "10K")
      (footprint "eagle-import:RESC2012X60_HS")
      (fields
        (field (name "MFR") "Yageo")
        (field (name "MPN") "RC0805JR-0710KL")
        (field (name "CREATOR") "Swanson")
        (field (name "REVIEWER") "Swanson")
      )
      (libsource (lib "eagle-import") (part "RESISTOR_SMD-2012-0805-10K"))
    )
    (comp (ref "R35")
      (value "10K")
      (footprint "eagle-import:RESC2012X60_HS")
      (fields
        (field (name "MFR") "Yageo")
        (field (name "MPN") "RC0805JR-0710KL")
        (field (name "CREATOR") "Swanson")
        (field (name "REVIEWER") "Swanson")
      )
      (libsource (lib "eagle-import") (part "RESISTOR_SMD-2012-0805-10K"))
    )
    (comp (ref "R36")
      (value "10K")
      (footprint "eagle-import:RESC2012X60_HS")
      (fields
        (field (name "MFR") "Yageo")
        (field (name "MPN") "RC0805JR-0710KL")
        (field (name "CREATOR") "Swanson")
        (field (name "REVIEWER") "Swanson")
      )
      (libsource (lib "eagle-import") (part "RESISTOR_SMD-2012-0805-10K"))
    )
    (comp (ref "R37")
      (value "10K")
      (footprint "eagle-import:RESC2012X60_HS")
      (fields
        (field (name "MFR") "Yageo")
        (field (name "MPN") "RC0805JR-0710KL")
        (field (name "CREATOR") "Swanson")
        (field (name "REVIEWER") "Swanson")
      )
      (libsource (lib "eagle-import") (part "RESISTOR_SMD-2012-0805-10K"))
    )
    (comp (ref "R38")
      (value "10K")
      (footprint "eagle-import:RESC2012X60_HS")
      (fields
        (field (name "MFR") "Yageo")
        (field (name "MPN") "RC0805JR-0710KL")
        (field (name "CREATOR") "Swanson")
        (field (name "REVIEWER") "Swanson")
      )
      (libsource (lib "eagle-import") (part "RESISTOR_SMD-2012-0805-10K"))
    )
    (comp (ref "R39")
      (value "5.1K")
      (footprint "eagle-import:RESC2012X60_HS")
      (fields
        (field (name "MFR") "Yageo")
        (field (name "MPN") "RC0805JR-075K1L")
        (field (name "CREATOR") "Swanson")
        (field (name "REVIEWER") "Swanson")
      )
      (libsource (lib "eagle-import") (part "RESISTOR_SMD-2012-0805-5.1K"))
    )
    (comp (ref "S1")
      (value "POWER-SWITCH-MFS201N-9-Z-SMD-EDGE")
      (footprint "eagle-import:JS102011SAQN")
      (fields
        (field (name "MFR") "C&K")
        (field (name "MPN") "JS102011SAQN")
        (field (name "CREATOR") "Swanson")
      )
      (libsource (lib "eagle-import") (part "POWER-SWITCH-MFS201N-9-Z-SMD-EDGE"))
    )
    (comp (ref "SW1")
      (value "PUSHBUTTON_-4.5X4.5")
      (footprint "eagle-import:4.5MM_TACTILE_SWITCH_TL3305AF160QG")
      (fields
        (field (name "MFR") "E-Switch")
        (field (name "MPN") "TL3305AF160QG")
        (field (name "CREATOR") "Swanson")
      )
      (libsource (lib "eagle-import") (part "PUSHBUTTON_-4.5X4.5"))
    )
    (comp (ref "U1")
      (value "ATMEGA128RFA1")
      (footprint "eagle-import:QFN-64")
      (fields
        (field (name "MFR") "Microchip Technology")
        (field (name "MPN") "ATMEGA128RFA1-ZU")
        (field (name "CREATOR") "Swanson")
        (field (name "REVIEWER") "Swanson")
      )
      (libsource (lib "eagle-import") (part "ATMEGA128RFA1"))
    )
    (comp (ref "U2")
      (value "IMU_LSM9DS1LSM9DS1")
      (footprint "eagle-import:IMU_LSM9DS1")
      (fields (field (name "CREATOR") "Rye Gleason"))
      (libsource (lib "eagle-import") (part "IMU_LSM9DS1LSM9DS1"))
    )
    (comp (ref "V1")
      (value "2.5V")
      (footprint "eagle-import:SOT23-DBV")
      (fields
        (field (name "MFR") "Texas Instruments")
        (field (name "MPN") "LP3985IM5X-2.5/NOPB")
        (field (name "CREATOR") "Swanson")
        (field (name "REVIEWER") "Swanson")
      )
      (libsource (lib "eagle-import") (part "TPS73633-DBVT2.5V"))
    )
    (comp (ref "W1")
      (value "NET_BRIDGENET_BRIDGE")
      (footprint "eagle-import:NET_BRIDGE")
      (fields (field (name "CREATOR") "Rye Gleason"))
      (libsource (lib "eagle-import") (part "NET_BRIDGENET_BRIDGE"))
    )
    (comp (ref "Y1")
      (value "CRYSTAL5X3")
      (footprint "eagle-import:CRYSTAL-SMD-5X3")
      (fields
        (field (name "MFR") "Abracon LLC")
        (field (name "MPN") "ABM3B-16.000MHZ-B2-T")
        (field (name "CREATOR") "Swanson")
        (field (name "REVIEWER") "Swanson")
      )
      (libsource (lib "eagle-import") (part "CRYSTAL5X3"))
    )
    (comp (ref "Z1")
      (value "DECORATION-LAYER-LABELS")
      (footprint "eagle-import:LAYER_LABELS")
      (libsource (lib "eagle-import") (part "DECORATION-LAYER-LABELS"))
    )
  )
  (nets
    (net (code "1") (name "2V5") (class "Default")
      (node (ref "C11") (pin "1") (pinfunction "1_1") (pintype "passive"))
      (node (ref "C12") (pin "1") (pinfunction "1_1") (pintype "passive"))
      (node (ref "C15") (pin "1") (pinfunction "1_1") (pintype "passive"))
      (node (ref "C17") (pin "1") (pinfunction "+_1") (pintype "passive"))
      (node (ref "C7") (pin "1") (pinfunction "1_1") (pintype "passive"))
      (node (ref "C8") (pin "1") (pinfunction "1_1") (pintype "passive"))
      (node (ref "C9") (pin "1") (pinfunction "1_1") (pintype "passive"))
      (node (ref "J3") (pin "3") (pinfunction "3_3") (pintype "passive"))
      (node (ref "J4") (pin "4") (pinfunction "4_4") (pintype "bidirectional"))
      (node (ref "R1") (pin "2") (pinfunction "2_2") (pintype "passive"))
      (node (ref "R4") (pin "1") (pinfunction "1_1") (pintype "passive"))
      (node (ref "R5") (pin "1") (pinfunction "1_1") (pintype "passive"))
      (node (ref "U1") (pin "23") (pinfunction "DEVDD_23") (pintype "bidirectional"))
      (node (ref "U1") (pin "34") (pinfunction "DEVDD_34") (pintype "bidirectional"))
      (node (ref "U1") (pin "44") (pinfunction "DEVDD_44") (pintype "bidirectional"))
      (node (ref "U1") (pin "54") (pinfunction "DEVDD_54") (pintype "bidirectional"))
      (node (ref "U1") (pin "59") (pinfunction "EVDD_59") (pintype "bidirectional"))
      (node (ref "U2") (pin "1") (pinfunction "VDDIO_1") (pintype "power_in"))
      (node (ref "U2") (pin "13") (pinfunction "DEN_A/G_13") (pintype "bidirectional"))
      (node (ref "U2") (pin "22") (pinfunction "VDD_22") (pintype "power_in"))
      (node (ref "U2") (pin "23") (pinfunction "VDD_23") (pintype "power_in"))
      (node (ref "U2") (pin "3") (pinfunction "VDDIO_3") (pintype "power_in"))
      (node (ref "U2") (pin "5") (pinfunction "SDO_A/G_5") (pintype "bidirectional"))
      (node (ref "U2") (pin "6") (pinfunction "SDO_M_6") (pintype "bidirectional"))
      (node (ref "U2") (pin "7") (pinfunction "CS_A/G_7") (pintype "bidirectional"))
      (node (ref "U2") (pin "8") (pinfunction "CS_M_8") (pintype "bidirectional"))
      (node (ref "V1") (pin "5") (pinfunction "OUT_5") (pintype "passive"))
    )
    (net (code "2") (name "3") (class "Default")
      (node (ref "J3") (pin "7") (pinfunction "7_7") (pintype "passive"))
      (node (ref "Q1") (pin "G") (pinfunction "G_G") (pintype "bidirectional"))
      (node (ref "R6") (pin "2") (pinfunction "2_2") (pintype "passive"))
      (node (ref "U1") (pin "49") (pinfunction "PE3(OC3A/AIN1)_49") (pintype "bidirectional"))
    )
    (net (code "3") (name "4") (class "Default")
      (node (ref "J3") (pin "5") (pinfunction "5_5") (pintype "passive"))
      (node (ref "Q2") (pin "G") (pinfunction "G_G") (pintype "bidirectional"))
      (node (ref "R7") (pin "2") (pinfunction "2_2") (pintype "passive"))
      (node (ref "U1") (pin "50") (pinfunction "PE4(OC3B/INT4)_50") (pintype "bidirectional"))
    )
    (net (code "4") (name "5") (class "Default")
      (node (ref "J3") (pin "4") (pinfunction "4_4") (pintype "passive"))
      (node (ref "Q3") (pin "G") (pinfunction "G_G") (pintype "bidirectional"))
      (node (ref "R8") (pin "2") (pinfunction "2_2") (pintype "passive"))
      (node (ref "U1") (pin "51") (pinfunction "PE5(OC3C/INT5)_51") (pintype "bidirectional"))
    )
    (net (code "5") (name "8") (class "Default")
      (node (ref "J3") (pin "1") (pinfunction "1_1") (pintype "passive"))
      (node (ref "Q4") (pin "G") (pinfunction "G_G") (pintype "bidirectional"))
      (node (ref "R9") (pin "2") (pinfunction "2_2") (pintype "passive"))
      (node (ref "U1") (pin "41") (pinfunction "PB5(OC1A/PCINT5)_41") (pintype "bidirectional"))
    )
    (net (code "6") (name "9") (class "Default")
      (node (ref "Q6") (pin "G") (pinfunction "G_G") (pintype "bidirectional"))
      (node (ref "R35") (pin "2") (pinfunction "2_2") (pintype "passive"))
      (node (ref "U1") (pin "40") (pinfunction "PB4(OC2A/PCINT4)_40") (pintype "bidirectional"))
    )
    (net (code "7") (name "19") (class "Default")
      (node (ref "Q5") (pin "G") (pinfunction "G_G") (pintype "bidirectional"))
      (node (ref "R36") (pin "2") (pinfunction "2_2") (pintype "passive"))
      (node (ref "U1") (pin "19") (pinfunction "PG5(OC0B)_19") (pintype "bidirectional"))
    )
    (net (code "8") (name "34") (class "Default")
      (node (ref "Q8") (pin "G") (pinfunction "G_G") (pintype "bidirectional"))
      (node (ref "R34") (pin "2") (pinfunction "2_2") (pintype "passive"))
      (node (ref "U1") (pin "42") (pinfunction "PB6(OC1B/PCINT6)_42") (pintype "bidirectional"))
    )
    (net (code "9") (name "35") (class "Default")
      (node (ref "Q7") (pin "G") (pinfunction "G_G") (pintype "bidirectional"))
      (node (ref "R37") (pin "2") (pinfunction "2_2") (pintype "passive"))
      (node (ref "U1") (pin "43") (pinfunction "PB7(OC0A/OC1C/PCINT7)_43") (pintype "bidirectional"))
    )
    (net (code "10") (name "A2") (class "Default")
      (node (ref "R39") (pin "2") (pinfunction "2_2") (pintype "passive"))
      (node (ref "U1") (pin "1") (pinfunction "PF2(ADC2/DIG2)_1") (pintype "bidirectional"))
    )
    (net (code "11") (name "BAT_GND") (class "Default")
      (node (ref "B3") (pin "2") (pinfunction "N_2") (pintype "bidirectional"))
      (node (ref "B3") (pin "G") (pinfunction "N_G") (pintype "bidirectional"))
      (node (ref "B3") (pin "G2") (pinfunction "N_G2") (pintype "bidirectional"))
      (node (ref "B3") (pin "G3") (pinfunction "N_G3") (pintype "bidirectional"))
      (node (ref "C14") (pin "2") (pinfunction "-_2") (pintype "passive"))
      (node (ref "C16") (pin "2") (pinfunction "2_2") (pintype "passive"))
      (node (ref "J3") (pin "9") (pinfunction "9_9") (pintype "passive"))
      (node (ref "M1") (pin "G1") (pinfunction "GND_G1") (pintype "bidirectional"))
      (node (ref "M1") (pin "G2") (pinfunction "GND_G2") (pintype "bidirectional"))
      (node (ref "M2") (pin "G1") (pinfunction "GND_G1") (pintype "bidirectional"))
      (node (ref "M2") (pin "G2") (pinfunction "GND_G2") (pintype "bidirectional"))
      (node (ref "M3") (pin "G1") (pinfunction "GND_G1") (pintype "bidirectional"))
      (node (ref "M3") (pin "G2") (pinfunction "GND_G2") (pintype "bidirectional"))
      (node (ref "M4") (pin "G1") (pinfunction "GND_G1") (pintype "bidirectional"))
      (node (ref "M4") (pin "G2") (pinfunction "GND_G2") (pintype "bidirectional"))
      (node (ref "Q1") (pin "S") (pinfunction "S_S") (pintype "bidirectional"))
      (node (ref "Q2") (pin "S") (pinfunction "S_S") (pintype "bidirectional"))
      (node (ref "Q3") (pin "S") (pinfunction "S_S") (pintype "bidirectional"))
      (node (ref "Q4") (pin "S") (pinfunction "S_S") (pintype "bidirectional"))
      (node (ref "Q5") (pin "S") (pinfunction "S_S") (pintype "bidirectional"))
      (node (ref "Q6") (pin "S") (pinfunction "S_S") (pintype "bidirectional"))
      (node (ref "Q7") (pin "S") (pinfunction "S_S") (pintype "bidirectional"))
      (node (ref "Q8") (pin "S") (pinfunction "S_S") (pintype "bidirectional"))
      (node (ref "S1") (pin "A") (pinfunction "OFF_A") (pintype "bidirectional"))
      (node (ref "V1") (pin "2") (pinfunction "GND_2") (pintype "input"))
      (node (ref "W1") (pin "1") (pinfunction "PAD_1_1") (pintype "passive"))
    )
    (net (code "12") (name "GND") (class "Default")
      (node (ref "B1") (pin "5") (pinfunction "GND_5") (pintype "bidirectional"))
      (node (ref "C1") (pin "1") (pinfunction "1_1") (pintype "passive"))
      (node (ref "C10") (pin "2") (pinfunction "2_2") (pintype "passive"))
      (node (ref "C11") (pin "2") (pinfunction "2_2") (pintype "passive"))
      (node (ref "C12") (pin "2") (pinfunction "2_2") (pintype "passive"))
      (node (ref "C13") (pin "2") (pinfunction "2_2") (pintype "passive"))
      (node (ref "C15") (pin "2") (pinfunction "2_2") (pintype "passive"))
      (node (ref "C17") (pin "2") (pinfunction "-_2") (pintype "passive"))
      (node (ref "C2") (pin "2") (pinfunction "2_2") (pintype "passive"))
      (node (ref "C3") (pin "2") (pinfunction "2_2") (pintype "passive"))
      (node (ref "C4") (pin "2") (pinfunction "2_2") (pintype "passive"))
      (node (ref "C5") (pin "2") (pinfunction "2_2") (pintype "passive"))
      (node (ref "C6") (pin "2") (pinfunction "2_2") (pintype "passive"))
      (node (ref "C7") (pin "2") (pinfunction "2_2") (pintype "passive"))
      (node (ref "C8") (pin "2") (pinfunction "2_2") (pintype "passive"))
      (node (ref "C9") (pin "2") (pinfunction "2_2") (pintype "passive"))
      (node (ref "D1") (pin "C") (pinfunction "C_C") (pintype "passive"))
      (node (ref "D2") (pin "C") (pinfunction "C_C") (pintype "passive"))
      (node (ref "J1") (pin "2") (pinfunction "2_2") (pintype "bidirectional"))
      (node (ref "J2") (pin "6") (pinfunction "6_6") (pintype "passive"))
      (node (ref "J3") (pin "10") (pinfunction "10_10") (pintype "passive"))
      (node (ref "J4") (pin "3") (pinfunction "3_3") (pintype "bidirectional"))
      (node (ref "R34") (pin "1") (pinfunction "1_1") (pintype "passive"))
      (node (ref "R35") (pin "1") (pinfunction "1_1") (pintype "passive"))
      (node (ref "R36") (pin "1") (pinfunction "1_1") (pintype "passive"))
      (node (ref "R37") (pin "1") (pinfunction "1_1") (pintype "passive"))
      (node (ref "R38") (pin "1") (pinfunction "1_1") (pintype "passive"))
      (node (ref "R6") (pin "1") (pinfunction "1_1") (pintype "passive"))
      (node (ref "R7") (pin "1") (pinfunction "1_1") (pintype "passive"))
      (node (ref "R8") (pin "1") (pinfunction "1_1") (pintype "passive"))
      (node (ref "R9") (pin "1") (pinfunction "1_1") (pintype "passive"))
      (node (ref "SW1") (pin "3") (pinfunction "2_3") (pintype "passive"))
      (node (ref "SW1") (pin "4") (pinfunction "2_4") (pintype "passive"))
      (node (ref "U1") (pin "10") (pinfunction "AVSS_RFN_10") (pintype "bidirectional"))
      (node (ref "U1") (pin "11") (pinfunction "TST_11") (pintype "bidirectional"))
      (node (ref "U1") (pin "20") (pinfunction "DVSS_20") (pintype "bidirectional"))
      (node (ref "U1") (pin "24") (pinfunction "DVSS_24") (pintype "bidirectional"))
      (node (ref "U1") (pin "33") (pinfunction "CLKI_33") (pintype "bidirectional"))
      (node (ref "U1") (pin "35") (pinfunction "DVSS_35") (pintype "bidirectional"))
      (node (ref "U1") (pin "45") (pinfunction "DVSS_45") (pintype "bidirectional"))
      (node (ref "U1") (pin "55") (pinfunction "DVSS_55") (pintype "bidirectional"))
      (node (ref "U1") (pin "58") (pinfunction "AVSS_58") (pintype "bidirectional"))
      (node (ref "U1") (pin "61") (pinfunction "AVSS_61") (pintype "bidirectional"))
      (node (ref "U1") (pin "7") (pinfunction "AVSS_RFP_7") (pintype "bidirectional"))
      (node (ref "U2") (pin "14") (pinfunction "GND_14") (pintype "bidirectional"))
      (node (ref "U2") (pin "15") (pinfunction "GND_15") (pintype "bidirectional"))
      (node (ref "U2") (pin "16") (pinfunction "GND_16") (pintype "bidirectional"))
      (node (ref "U2") (pin "17") (pinfunction "GND_17") (pintype "bidirectional"))
      (node (ref "U2") (pin "18") (pinfunction "GND_18") (pintype "bidirectional"))
      (node (ref "U2") (pin "19") (pinfunction "GND_19") (pintype "bidirectional"))
      (node (ref "U2") (pin "20") (pinfunction "GND_20") (pintype "bidirectional"))
      (node (ref "W1") (pin "2") (pinfunction "PAD_2_2") (pintype "passive"))
    )
    (net (code "13") (name "MISO") (class "Default")
      (node (ref "J2") (pin "1") (pinfunction "1_1") (pintype "passive"))
      (node (ref "U1") (pin "39") (pinfunction "PB3(MISO/PDO/PCINT3)_39") (pintype "bidirectional"))
    )
    (net (code "14") (name "MOSI") (class "Default")
      (node (ref "J2") (pin "4") (pinfunction "4_4") (pintype "passive"))
      (node (ref "U1") (pin "38") (pinfunction "PB2(MOSI/PDI/PCINT2)_38") (pintype "bidirectional"))
    )
    (net (code "15") (name "Net-(A1-SIGNAL)") (class "Default")
      (node (ref "A1") (pin "FEED") (pinfunction "SIGNAL_FEED") (pintype "bidirectional"))
      (node (ref "B1") (pin "1") (pinfunction "IN_1") (pintype "bidirectional"))
      (node (ref "C2") (pin "1") (pinfunction "1_1") (pintype "passive"))
    )
    (net (code "16") (name "Net-(B1-GND-Pad2)") (class "Default")
      (node (ref "B1") (pin "2") (pinfunction "GND_2") (pintype "bidirectional"))
      (node (ref "C1") (pin "2") (pinfunction "2_2") (pintype "passive"))
    )
    (net (code "17") (name "Net-(B1-OUT1)") (class "Default")
      (node (ref "B1") (pin "4") (pinfunction "OUT1_4") (pintype "bidirectional"))
      (node (ref "U1") (pin "8") (pinfunction "RFP_8") (pintype "bidirectional"))
    )
    (net (code "18") (name "Net-(B1-OUT2)") (class "Default")
      (node (ref "B1") (pin "3") (pinfunction "OUT2_3") (pintype "bidirectional"))
      (node (ref "U1") (pin "9") (pinfunction "RFN_9") (pintype "bidirectional"))
    )
    (net (code "19") (name "Net-(C3-Pad1)") (class "Default")
      (node (ref "C3") (pin "1") (pinfunction "1_1") (pintype "passive"))
      (node (ref "U1") (pin "21") (pinfunction "DVDD_21") (pintype "bidirectional"))
      (node (ref "U1") (pin "22") (pinfunction "DVDD_22") (pintype "bidirectional"))
    )
    (net (code "20") (name "Net-(C18-Pad1)") (class "Default")
      (node (ref "C18") (pin "1") (pinfunction "1_1") (pintype "passive"))
      (node (ref "J1") (pin "1") (pinfunction "1_1") (pintype "bidirectional"))
    )
    (net (code "21") (name "Net-(D1-PadA)") (class "Default")
      (node (ref "D1") (pin "A") (pinfunction "A_A") (pintype "passive"))
      (node (ref "R3") (pin "1") (pinfunction "1_1") (pintype "passive"))
    )
    (net (code "22") (name "Net-(D2-PadA)") (class "Default")
      (node (ref "D2") (pin "A") (pinfunction "A_A") (pintype "passive"))
      (node (ref "R2") (pin "1") (pinfunction "1_1") (pintype "passive"))
    )
    (net (code "23") (name "Net-(D3-A)") (class "Default")
      (node (ref "D3") (pin "2") (pinfunction "A_2") (pintype "passive"))
      (node (ref "M1") (pin "2") (pinfunction "V-_2") (pintype "bidirectional"))
      (node (ref "Q1") (pin "D") (pinfunction "D_D") (pintype "bidirectional"))
    )
    (net (code "24") (name "Net-(D4-A)") (class "Default")
      (node (ref "D4") (pin "2") (pinfunction "A_2") (pintype "passive"))
      (node (ref "M2") (pin "2") (pinfunction "V-_2") (pintype "bidirectional"))
      (node (ref "Q2") (pin "D") (pinfunction "D_D") (pintype "bidirectional"))
    )
    (net (code "25") (name "Net-(D5-A)") (class "Default")
      (node (ref "D5") (pin "2") (pinfunction "A_2") (pintype "passive"))
      (node (ref "M3") (pin "2") (pinfunction "V-_2") (pintype "bidirectional"))
      (node (ref "Q3") (pin "D") (pinfunction "D_D") (pintype "bidirectional"))
    )
    (net (code "26") (name "Net-(D6-A)") (class "Default")
      (node (ref "D6") (pin "2") (pinfunction "A_2") (pintype "passive"))
      (node (ref "M4") (pin "2") (pinfunction "V-_2") (pintype "bidirectional"))
      (node (ref "Q4") (pin "D") (pinfunction "D_D") (pintype "bidirectional"))
    )
    (net (code "27") (name "Net-(D7A-C)") (class "Default")
      (node (ref "D7") (pin "2") (pinfunction "C_2") (pintype "passive"))
      (node (ref "R10") (pin "1") (pinfunction "1_1") (pintype "passive"))
    )
    (net (code "28") (name "Net-(D7B-C)") (class "Default")
      (node (ref "D7") (pin "3") (pinfunction "C_3") (pintype "passive"))
      (node (ref "R11") (pin "1") (pinfunction "1_1") (pintype "passive"))
    )
    (net (code "29") (name "Net-(D8A-C)") (class "Default")
      (node (ref "D8") (pin "2") (pinfunction "C_2") (pintype "passive"))
      (node (ref "R12") (pin "1") (pinfunction "1_1") (pintype "passive"))
    )
    (net (code "30") (name "Net-(D8B-C)") (class "Default")
      (node (ref "D8") (pin "3") (pinfunction "C_3") (pintype "passive"))
      (node (ref "R13") (pin "1") (pinfunction "1_1") (pintype "passive"))
    )
    (net (code "31") (name "Net-(D9A-C)") (class "Default")
      (node (ref "D9") (pin "2") (pinfunction "C_2") (pintype "passive"))
      (node (ref "R14") (pin "1") (pinfunction "1_1") (pintype "passive"))
    )
    (net (code "32") (name "Net-(D9B-C)") (class "Default")
      (node (ref "D9") (pin "3") (pinfunction "C_3") (pintype "passive"))
      (node (ref "R15") (pin "1") (pinfunction "1_1") (pintype "passive"))
    )
    (net (code "33") (name "Net-(D10A-C)") (class "Default")
      (node (ref "D10") (pin "2") (pinfunction "C_2") (pintype "passive"))
      (node (ref "R16") (pin "1") (pinfunction "1_1") (pintype "passive"))
    )
    (net (code "34") (name "Net-(D10B-C)") (class "Default")
      (node (ref "D10") (pin "3") (pinfunction "C_3") (pintype "passive"))
      (node (ref "R17") (pin "1") (pinfunction "1_1") (pintype "passive"))
    )
    (net (code "35") (name "Net-(D11A-C)") (class "Default")
      (node (ref "D11") (pin "2") (pinfunction "C_2") (pintype "passive"))
      (node (ref "R18") (pin "1") (pinfunction "1_1") (pintype "passive"))
    )
    (net (code "36") (name "Net-(D11B-C)") (class "Default")
      (node (ref "D11") (pin "3") (pinfunction "C_3") (pintype "passive"))
      (node (ref "R19") (pin "1") (pinfunction "1_1") (pintype "passive"))
    )
    (net (code "37") (name "Net-(D12A-C)") (class "Default")
      (node (ref "D12") (pin "2") (pinfunction "C_2") (pintype "passive"))
      (node (ref "R20") (pin "1") (pinfunction "1_1") (pintype "passive"))
    )
    (net (code "38") (name "Net-(D12B-C)") (class "Default")
      (node (ref "D12") (pin "3") (pinfunction "C_3") (pintype "passive"))
      (node (ref "R21") (pin "1") (pinfunction "1_1") (pintype "passive"))
    )
    (net (code "39") (name "Net-(D13A-C)") (class "Default")
      (node (ref "D13") (pin "2") (pinfunction "C_2") (pintype "passive"))
      (node (ref "R22") (pin "1") (pinfunction "1_1") (pintype "passive"))
    )
    (net (code "40") (name "Net-(D13B-C)") (class "Default")
      (node (ref "D13") (pin "3") (pinfunction "C_3") (pintype "passive"))
      (node (ref "R23") (pin "1") (pinfunction "1_1") (pintype "passive"))
    )
    (net (code "41") (name "Net-(D14A-C)") (class "Default")
      (node (ref "D14") (pin "2") (pinfunction "C_2") (pintype "passive"))
      (node (ref "R24") (pin "1") (pinfunction "1_1") (pintype "passive"))
    )
    (net (code "42") (name "Net-(D14B-C)") (class "Default")
      (node (ref "D14") (pin "3") (pinfunction "C_3") (pintype "passive"))
      (node (ref "R25") (pin "1") (pinfunction "1_1") (pintype "passive"))
    )
    (net (code "43") (name "Net-(D15A-C)") (class "Default")
      (node (ref "D15") (pin "2") (pinfunction "C_2") (pintype "passive"))
      (node (ref "R26") (pin "1") (pinfunction "1_1") (pintype "passive"))
    )
    (net (code "44") (name "Net-(D15B-C)") (class "Default")
      (node (ref "D15") (pin "3") (pinfunction "C_3") (pintype "passive"))
      (node (ref "R27") (pin "1") (pinfunction "1_1") (pintype "passive"))
    )
    (net (code "45") (name "Net-(D16A-C)") (class "Default")
      (node (ref "D16") (pin "2") (pinfunction "C_2") (pintype "passive"))
      (node (ref "R31") (pin "1") (pinfunction "1_1") (pintype "passive"))
    )
    (net (code "46") (name "Net-(D16B-C)") (class "Default")
      (node (ref "D16") (pin "3") (pinfunction "C_3") (pintype "passive"))
      (node (ref "R28") (pin "1") (pinfunction "1_1") (pintype "passive"))
    )
    (net (code "47") (name "Net-(D17A-C)") (class "Default")
      (node (ref "D17") (pin "2") (pinfunction "C_2") (pintype "passive"))
      (node (ref "R32") (pin "1") (pinfunction "1_1") (pintype "passive"))
    )
    (net (code "48") (name "Net-(D17B-C)") (class "Default")
      (node (ref "D17") (pin "3") (pinfunction "C_3") (pintype "passive"))
      (node (ref "R29") (pin "1") (pinfunction "1_1") (pintype "passive"))
    )
    (net (code "49") (name "Net-(D18A-C)") (class "Default")
      (node (ref "D18") (pin "2") (pinfunction "C_2") (pintype "passive"))
      (node (ref "R33") (pin "1") (pinfunction "1_1") (pintype "passive"))
    )
    (net (code "50") (name "Net-(D18B-C)") (class "Default")
      (node (ref "D18") (pin "3") (pinfunction "C_3") (pintype "passive"))
      (node (ref "R30") (pin "1") (pinfunction "1_1") (pintype "passive"))
    )
    (net (code "51") (name "Net-(Q5-PadD)") (class "Default")
      (node (ref "Q5") (pin "D") (pinfunction "D_D") (pintype "bidirectional"))
      (node (ref "R10") (pin "2") (pinfunction "2_2") (pintype "passive"))
      (node (ref "R12") (pin "2") (pinfunction "2_2") (pintype "passive"))
      (node (ref "R14") (pin "2") (pinfunction "2_2") (pintype "passive"))
      (node (ref "R22") (pin "2") (pinfunction "2_2") (pintype "passive"))
      (node (ref "R24") (pin "2") (pinfunction "2_2") (pintype "passive"))
      (node (ref "R26") (pin "2") (pinfunction "2_2") (pintype "passive"))
    )
    (net (code "52") (name "Net-(Q6-PadD)") (class "Default")
      (node (ref "Q6") (pin "D") (pinfunction "D_D") (pintype "bidirectional"))
      (node (ref "R11") (pin "2") (pinfunction "2_2") (pintype "passive"))
      (node (ref "R13") (pin "2") (pinfunction "2_2") (pintype "passive"))
      (node (ref "R15") (pin "2") (pinfunction "2_2") (pintype "passive"))
      (node (ref "R23") (pin "2") (pinfunction "2_2") (pintype "passive"))
      (node (ref "R25") (pin "2") (pinfunction "2_2") (pintype "passive"))
      (node (ref "R27") (pin "2") (pinfunction "2_2") (pintype "passive"))
    )
    (net (code "53") (name "Net-(Q7-PadD)") (class "Default")
      (node (ref "Q7") (pin "D") (pinfunction "D_D") (pintype "bidirectional"))
      (node (ref "R16") (pin "2") (pinfunction "2_2") (pintype "passive"))
      (node (ref "R18") (pin "2") (pinfunction "2_2") (pintype "passive"))
      (node (ref "R20") (pin "2") (pinfunction "2_2") (pintype "passive"))
      (node (ref "R31") (pin "2") (pinfunction "2_2") (pintype "passive"))
      (node (ref "R32") (pin "2") (pinfunction "2_2") (pintype "passive"))
      (node (ref "R33") (pin "2") (pinfunction "2_2") (pintype "passive"))
    )
    (net (code "54") (name "Net-(Q8-PadD)") (class "Default")
      (node (ref "Q8") (pin "D") (pinfunction "D_D") (pintype "bidirectional"))
      (node (ref "R17") (pin "2") (pinfunction "2_2") (pintype "passive"))
      (node (ref "R19") (pin "2") (pinfunction "2_2") (pintype "passive"))
      (node (ref "R21") (pin "2") (pinfunction "2_2") (pintype "passive"))
      (node (ref "R28") (pin "2") (pinfunction "2_2") (pintype "passive"))
      (node (ref "R29") (pin "2") (pinfunction "2_2") (pintype "passive"))
      (node (ref "R30") (pin "2") (pinfunction "2_2") (pintype "passive"))
    )
    (net (code "55") (name "Net-(U1-AVDD)") (class "Default")
      (node (ref "C4") (pin "1") (pinfunction "1_1") (pintype "passive"))
      (node (ref "U1") (pin "60") (pinfunction "AVDD_60") (pintype "bidirectional"))
    )
    (net (code "56") (name "Net-(U1-XTAL1)") (class "Default")
      (node (ref "C5") (pin "1") (pinfunction "1_1") (pintype "passive"))
      (node (ref "U1") (pin "57") (pinfunction "XTAL1_57") (pintype "bidirectional"))
      (node (ref "Y1") (pin "3") (pinfunction "2_3") (pintype "passive"))
    )
    (net (code "57") (name "Net-(U1-XTAL2)") (class "Default")
      (node (ref "C6") (pin "1") (pinfunction "1_1") (pintype "passive"))
      (node (ref "U1") (pin "56") (pinfunction "XTAL2_56") (pintype "bidirectional"))
      (node (ref "Y1") (pin "1") (pinfunction "1_1") (pintype "passive"))
    )
    (net (code "58") (name "Net-(U2-C1)") (class "Default")
      (node (ref "C10") (pin "1") (pinfunction "1_1") (pintype "passive"))
      (node (ref "U2") (pin "24") (pinfunction "C1_24") (pintype "bidirectional"))
    )
    (net (code "59") (name "Net-(U2-CAP)") (class "Default")
      (node (ref "C13") (pin "1") (pinfunction "1_1") (pintype "passive"))
      (node (ref "U2") (pin "21") (pinfunction "CAP_21") (pintype "bidirectional"))
    )
    (net (code "60") (name "Net-(V1-EN)") (class "Default")
      (node (ref "S1") (pin "C") (pinfunction "C_C") (pintype "bidirectional"))
      (node (ref "V1") (pin "3") (pinfunction "EN_3") (pintype "input"))
    )
    (net (code "61") (name "PG0") (class "Default")
      (node (ref "R2") (pin "2") (pinfunction "2_2") (pintype "passive"))
      (node (ref "U1") (pin "14") (pinfunction "PG0(DIG3)_14") (pintype "bidirectional"))
    )
    (net (code "62") (name "PG1") (class "Default")
      (node (ref "R3") (pin "2") (pinfunction "2_2") (pintype "passive"))
      (node (ref "U1") (pin "15") (pinfunction "PG1(DIG1)_15") (pintype "bidirectional"))
    )
    (net (code "63") (name "RESET") (class "Default")
      (node (ref "C18") (pin "2") (pinfunction "2_2") (pintype "passive"))
      (node (ref "J2") (pin "5") (pinfunction "5_5") (pintype "passive"))
      (node (ref "R1") (pin "1") (pinfunction "1_1") (pintype "passive"))
      (node (ref "SW1") (pin "1") (pinfunction "1_1") (pintype "passive"))
      (node (ref "SW1") (pin "2") (pinfunction "1_2") (pintype "passive"))
      (node (ref "U1") (pin "12") (pinfunction "RSTN_12") (pintype "bidirectional"))
    )
    (net (code "64") (name "RX0") (class "Default")
      (node (ref "J1") (pin "3") (pinfunction "3_3") (pintype "bidirectional"))
      (node (ref "U1") (pin "46") (pinfunction "PE0(RXD0/PCINT8)_46") (pintype "bidirectional"))
    )
    (net (code "65") (name "SCK") (class "Default")
      (node (ref "J2") (pin "3") (pinfunction "3_3") (pintype "passive"))
      (node (ref "U1") (pin "37") (pinfunction "PB1(SCK/PCINT1)_37") (pintype "bidirectional"))
    )
    (net (code "66") (name "SCL") (class "Default")
      (node (ref "J3") (pin "2") (pinfunction "2_2") (pintype "passive"))
      (node (ref "J4") (pin "2") (pinfunction "2_2") (pintype "bidirectional"))
      (node (ref "R5") (pin "2") (pinfunction "2_2") (pintype "passive"))
      (node (ref "U1") (pin "25") (pinfunction "PD0(SCL/INT0)_25") (pintype "bidirectional"))
      (node (ref "U2") (pin "2") (pinfunction "SCL/SPC_2") (pintype "bidirectional"))
    )
    (net (code "67") (name "SDA") (class "Default")
      (node (ref "J3") (pin "8") (pinfunction "8_8") (pintype "passive"))
      (node (ref "J4") (pin "1") (pinfunction "1_1") (pintype "bidirectional"))
      (node (ref "R4") (pin "2") (pinfunction "2_2") (pintype "passive"))
      (node (ref "U1") (pin "26") (pinfunction "PD1(SDA/INT1)_26") (pintype "bidirectional"))
      (node (ref "U2") (pin "4") (pinfunction "SDA/SDI/SDO_4") (pintype "bidirectional"))
    )
    (net (code "68") (name "TX0") (class "Default")
      (node (ref "J1") (pin "4") (pinfunction "4_4") (pintype "bidirectional"))
      (node (ref "U1") (pin "47") (pinfunction "PE1(TXD0)_47") (pintype "bidirectional"))
    )
    (net (code "69") (name "VBAT") (class "Default")
      (node (ref "B3") (pin "1") (pinfunction "P_1") (pintype "bidirectional"))
      (node (ref "B3") (pin "P") (pinfunction "P_P") (pintype "bidirectional"))
      (node (ref "C14") (pin "1") (pinfunction "+_1") (pintype "passive"))
      (node (ref "C16") (pin "1") (pinfunction "1_1") (pintype "passive"))
      (node (ref "D10") (pin "1") (pinfunction "A_1") (pintype "passive"))
      (node (ref "D10") (pin "4") (pinfunction "A_4") (pintype "passive"))
      (node (ref "D11") (pin "1") (pinfunction "A_1") (pintype "passive"))
      (node (ref "D11") (pin "4") (pinfunction "A_4") (pintype "passive"))
      (node (ref "D12") (pin "1") (pinfunction "A_1") (pintype "passive"))
      (node (ref "D12") (pin "4") (pinfunction "A_4") (pintype "passive"))
      (node (ref "D13") (pin "1") (pinfunction "A_1") (pintype "passive"))
      (node (ref "D13") (pin "4") (pinfunction "A_4") (pintype "passive"))
      (node (ref "D14") (pin "1") (pinfunction "A_1") (pintype "passive"))
      (node (ref "D14") (pin "4") (pinfunction "A_4") (pintype "passive"))
      (node (ref "D15") (pin "1") (pinfunction "A_1") (pintype "passive"))
      (node (ref "D15") (pin "4") (pinfunction "A_4") (pintype "passive"))
      (node (ref "D16") (pin "1") (pinfunction "A_1") (pintype "passive"))
      (node (ref "D16") (pin "4") (pinfunction "A_4") (pintype "passive"))
      (node (ref "D17") (pin "1") (pinfunction "A_1") (pintype "passive"))
      (node (ref "D17") (pin "4") (pinfunction "A_4") (pintype "passive"))
      (node (ref "D18") (pin "1") (pinfunction "A_1") (pintype "passive"))
      (node (ref "D18") (pin "4") (pinfunction "A_4") (pintype "passive"))
      (node (ref "D3") (pin "1") (pinfunction "C_1") (pintype "passive"))
      (node (ref "D4") (pin "1") (pinfunction "C_1") (pintype "passive"))
      (node (ref "D5") (pin "1") (pinfunction "C_1") (pintype "passive"))
      (node (ref "D6") (pin "1") (pinfunction "C_1") (pintype "passive"))
      (node (ref "D7") (pin "1") (pinfunction "A_1") (pintype "passive"))
      (node (ref "D7") (pin "4") (pinfunction "A_4") (pintype "passive"))
      (node (ref "D8") (pin "1") (pinfunction "A_1") (pintype "passive"))
      (node (ref "D8") (pin "4") (pinfunction "A_4") (pintype "passive"))
      (node (ref "D9") (pin "1") (pinfunction "A_1") (pintype "passive"))
      (node (ref "D9") (pin "4") (pinfunction "A_4") (pintype "passive"))
      (node (ref "J3") (pin "6") (pinfunction "6_6") (pintype "passive"))
      (node (ref "M1") (pin "1") (pinfunction "V+_1") (pintype "bidirectional"))
      (node (ref "M2") (pin "1") (pinfunction "V+_1") (pintype "bidirectional"))
      (node (ref "M3") (pin "1") (pinfunction "V+_1") (pintype "bidirectional"))
      (node (ref "M4") (pin "1") (pinfunction "V+_1") (pintype "bidirectional"))
      (node (ref "R38") (pin "2") (pinfunction "2_2") (pintype "passive"))
      (node (ref "R39") (pin "1") (pinfunction "1_1") (pintype "passive"))
      (node (ref "S1") (pin "B") (pinfunction "ON_B") (pintype "bidirectional"))
      (node (ref "V1") (pin "1") (pinfunction "IN_1") (pintype "input"))
    )
    (net (code "70") (name "unconnected-(J2-Pad2)") (class "Default")
      (node (ref "J2") (pin "2") (pinfunction "2_2") (pintype "passive"))
    )
    (net (code "71") (name "unconnected-(U1-AREF-Pad62)") (class "Default")
      (node (ref "U1") (pin "62") (pinfunction "AREF_62") (pintype "bidirectional"))
    )
    (net (code "72") (name "unconnected-(U1-PB0(SSN{slash}PCINT0)-Pad36)") (class "Default")
      (node (ref "U1") (pin "36") (pinfunction "PB0(SSN/PCINT0)_36") (pintype "bidirectional"))
    )
    (net (code "73") (name "unconnected-(U1-PD2(RXD1{slash}INT2)-Pad27)") (class "Default")
      (node (ref "U1") (pin "27") (pinfunction "PD2(RXD1/INT2)_27") (pintype "bidirectional"))
    )
    (net (code "74") (name "unconnected-(U1-PD3(TXD1{slash}INT3)-Pad28)") (class "Default")
      (node (ref "U1") (pin "28") (pinfunction "PD3(TXD1/INT3)_28") (pintype "bidirectional"))
    )
    (net (code "75") (name "unconnected-(U1-PD4(ICP1)-Pad29)") (class "Default")
      (node (ref "U1") (pin "29") (pinfunction "PD4(ICP1)_29") (pintype "bidirectional"))
    )
    (net (code "76") (name "unconnected-(U1-PD5(XCK1)-Pad30)") (class "Default")
      (node (ref "U1") (pin "30") (pinfunction "PD5(XCK1)_30") (pintype "bidirectional"))
    )
    (net (code "77") (name "unconnected-(U1-PD6(T1)-Pad31)") (class "Default")
      (node (ref "U1") (pin "31") (pinfunction "PD6(T1)_31") (pintype "bidirectional"))
    )
    (net (code "78") (name "unconnected-(U1-PD7(T0)-Pad32)") (class "Default")
      (node (ref "U1") (pin "32") (pinfunction "PD7(T0)_32") (pintype "bidirectional"))
    )
    (net (code "79") (name "unconnected-(U1-PE2(XCK0{slash}AIN0)-Pad48)") (class "Default")
      (node (ref "U1") (pin "48") (pinfunction "PE2(XCK0/AIN0)_48") (pintype "bidirectional"))
    )
    (net (code "80") (name "unconnected-(U1-PE6(T3{slash}INT6)-Pad52)") (class "Default")
      (node (ref "U1") (pin "52") (pinfunction "PE6(T3/INT6)_52") (pintype "bidirectional"))
    )
    (net (code "81") (name "unconnected-(U1-PE7(ICP3{slash}INT7{slash}CLKO)-Pad53)") (class "Default")
      (node (ref "U1") (pin "53") (pinfunction "PE7(ICP3/INT7/CLKO)_53") (pintype "bidirectional"))
    )
    (net (code "82") (name "unconnected-(U1-PF0(ADC0)-Pad63)") (class "Default")
      (node (ref "U1") (pin "63") (pinfunction "PF0(ADC0)_63") (pintype "bidirectional"))
    )
    (net (code "83") (name "unconnected-(U1-PF1(ADC1)-Pad64)") (class "Default")
      (node (ref "U1") (pin "64") (pinfunction "PF1(ADC1)_64") (pintype "bidirectional"))
    )
    (net (code "84") (name "unconnected-(U1-PF3(ADC3{slash}DIG4)-Pad2)") (class "Default")
      (node (ref "U1") (pin "2") (pinfunction "PF3(ADC3/DIG4)_2") (pintype "bidirectional"))
    )
    (net (code "85") (name "unconnected-(U1-PF4(ADC4{slash}TCK)-Pad3)") (class "Default")
      (node (ref "U1") (pin "3") (pinfunction "PF4(ADC4/TCK)_3") (pintype "bidirectional"))
    )
    (net (code "86") (name "unconnected-(U1-PF5(ADC5{slash}TMS)-Pad4)") (class "Default")
      (node (ref "U1") (pin "4") (pinfunction "PF5(ADC5/TMS)_4") (pintype "bidirectional"))
    )
    (net (code "87") (name "unconnected-(U1-PF6(ADC6{slash}TDO)-Pad5)") (class "Default")
      (node (ref "U1") (pin "5") (pinfunction "PF6(ADC6/TDO)_5") (pintype "bidirectional"))
    )
    (net (code "88") (name "unconnected-(U1-PF7(ADC7{slash}TDI)-Pad6)") (class "Default")
      (node (ref "U1") (pin "6") (pinfunction "PF7(ADC7/TDI)_6") (pintype "bidirectional"))
    )
    (net (code "89") (name "unconnected-(U1-PG2(AMR)-Pad16)") (class "Default")
      (node (ref "U1") (pin "16") (pinfunction "PG2(AMR)_16") (pintype "bidirectional"))
    )
    (net (code "90") (name "unconnected-(U1-PG3(TOSC2)-Pad17)") (class "Default")
      (node (ref "U1") (pin "17") (pinfunction "PG3(TOSC2)_17") (pintype "bidirectional"))
    )
    (net (code "91") (name "unconnected-(U1-PG4(TOSC1)-Pad18)") (class "Default")
      (node (ref "U1") (pin "18") (pinfunction "PG4(TOSC1)_18") (pintype "bidirectional"))
    )
    (net (code "92") (name "unconnected-(U1-RSTON-Pad13)") (class "Default")
      (node (ref "U1") (pin "13") (pinfunction "RSTON_13") (pintype "bidirectional"))
    )
    (net (code "93") (name "unconnected-(U2-DRDY_M-Pad9)") (class "Default")
      (node (ref "U2") (pin "9") (pinfunction "DRDY_M_9") (pintype "bidirectional"))
    )
    (net (code "94") (name "unconnected-(U2-INT1_A{slash}G-Pad11)") (class "Default")
      (node (ref "U2") (pin "11") (pinfunction "INT1_A/G_11") (pintype "bidirectional"))
    )
    (net (code "95") (name "unconnected-(U2-INT2_A{slash}G-Pad12)") (class "Default")
      (node (ref "U2") (pin "12") (pinfunction "INT2_A/G_12") (pintype "bidirectional"))
    )
    (net (code "96") (name "unconnected-(U2-INT_M-Pad10)") (class "Default")
      (node (ref "U2") (pin "10") (pinfunction "INT_M_10") (pintype "bidirectional"))
    )
    (net (code "97") (name "unconnected-(V1-NC{slash}FB-Pad4)") (class "Default")
      (node (ref "V1") (pin "4") (pinfunction "NC/FB_4") (pintype "passive"))
    )
  )
)
